# LCD9pin.net
KiCad netlist of a schematic drawn in Altium Designer
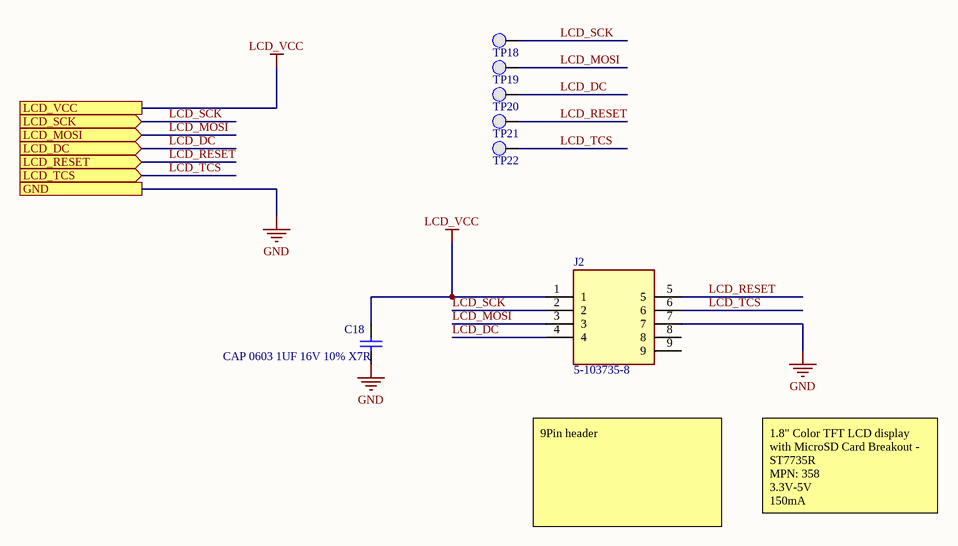
[diagram p0: LCD9pin.SchDoc]

(export (version "E")
  (design (tool "Eeschema 10.0.6"))
  (components
    (comp (ref "C18")
      (value "CAP 0603 1UF 16V 10% X7R")
      (footprint "0603_CAP")
      (description "Capacitor Surface Mount 0603 Footprint 1UF 16V 10% Tolerance Ceramic X7R")
      (fields (field (name "MANUFACTURER") "Various"))
      (libsource (lib "University of Pennsylvania (ESE Labs)") (part "cap"))
    )
    (comp (ref "J2")
      (value "5-103735-8")
      (footprint "PcbLib1:TE_5-103735-8")
      (description "Conn Shrouded Header HDR 9 POS 2.54mm Solder ST Thru-Hole Box/Tube")
      (fields (field (name "MF") "TE Connectivity") (field (name "DIGI-KEY_PART_NUMBER") "A33940-ND"))
      (libsource (lib "Schlib1") (part "5-103735-8"))
    )
    (comp (ref "TP18")
      (value "Test Point 0.1\"")
      (footprint "Test Point 0.1\"-Footprint-1")
      (libsource (lib "University of Pennsylvania (ESE Labs)") (part "Test Point 0.1{dblquote}-Symbol-1"))
    )
    (comp (ref "TP19")
      (value "Test Point 0.1\"")
      (footprint "Test Point 0.1\"-Footprint-1")
      (libsource (lib "University of Pennsylvania (ESE Labs)") (part "Test Point 0.1{dblquote}-Symbol-1"))
    )
    (comp (ref "TP20")
      (value "Test Point 0.1\"")
      (footprint "Test Point 0.1\"-Footprint-1")
      (libsource (lib "University of Pennsylvania (ESE Labs)") (part "Test Point 0.1{dblquote}-Symbol-1"))
    )
    (comp (ref "TP21")
      (value "Test Point 0.1\"")
      (footprint "Test Point 0.1\"-Footprint-1")
      (libsource (lib "University of Pennsylvania (ESE Labs)") (part "Test Point 0.1{dblquote}-Symbol-1"))
    )
    (comp (ref "TP22")
      (value "Test Point 0.1\"")
      (footprint "Test Point 0.1\"-Footprint-1")
      (libsource (lib "University of Pennsylvania (ESE Labs)") (part "Test Point 0.1{dblquote}-Symbol-1"))
    )
  )
  (nets
    (net (code "1") (name "/LCD_DC") (class "Default")
      (node (ref "J2") (pin "4") (pinfunction "4_4") (pintype "passive"))
      (node (ref "TP20") (pin "1") (pinfunction "PAD_1") (pintype "passive"))
    )
    (net (code "2") (name "/LCD_MOSI") (class "Default")
      (node (ref "J2") (pin "3") (pinfunction "3_3") (pintype "passive"))
      (node (ref "TP19") (pin "1") (pinfunction "PAD_1") (pintype "passive"))
    )
    (net (code "3") (name "/LCD_RESET") (class "Default")
      (node (ref "J2") (pin "5") (pinfunction "5_5") (pintype "passive"))
      (node (ref "TP21") (pin "1") (pinfunction "PAD_1") (pintype "passive"))
    )
    (net (code "4") (name "/LCD_SCK") (class "Default")
      (node (ref "J2") (pin "2") (pinfunction "2_2") (pintype "passive"))
      (node (ref "TP18") (pin "1") (pinfunction "PAD_1") (pintype "passive"))
    )
    (net (code "5") (name "/LCD_TCS") (class "Default")
      (node (ref "J2") (pin "6") (pinfunction "6_6") (pintype "passive"))
      (node (ref "TP22") (pin "1") (pinfunction "PAD_1") (pintype "passive"))
    )
    (net (code "6") (name "GND") (class "Default")
      (node (ref "C18") (pin "1") (pinfunction "1_1") (pintype "passive"))
      (node (ref "J2") (pin "7") (pinfunction "7_7") (pintype "passive"))
    )
    (net (code "7") (name "LCD_VCC") (class "Default")
      (node (ref "C18") (pin "2") (pinfunction "2_2") (pintype "passive"))
      (node (ref "J2") (pin "1") (pinfunction "1_1") (pintype "passive"))
    )
    (net (code "8") (name "unconnected-(J2-Pad8)") (class "Default")
      (node (ref "J2") (pin "8") (pinfunction "8_8") (pintype "passive"))
    )
    (net (code "9") (name "unconnected-(J2-Pad9)") (class "Default")
      (node (ref "J2") (pin "9") (pinfunction "9_9") (pintype "passive"))
    )
  )
)
